# pre_amplify.net
KiCad netlist of a schematic drawn in Altium Designer
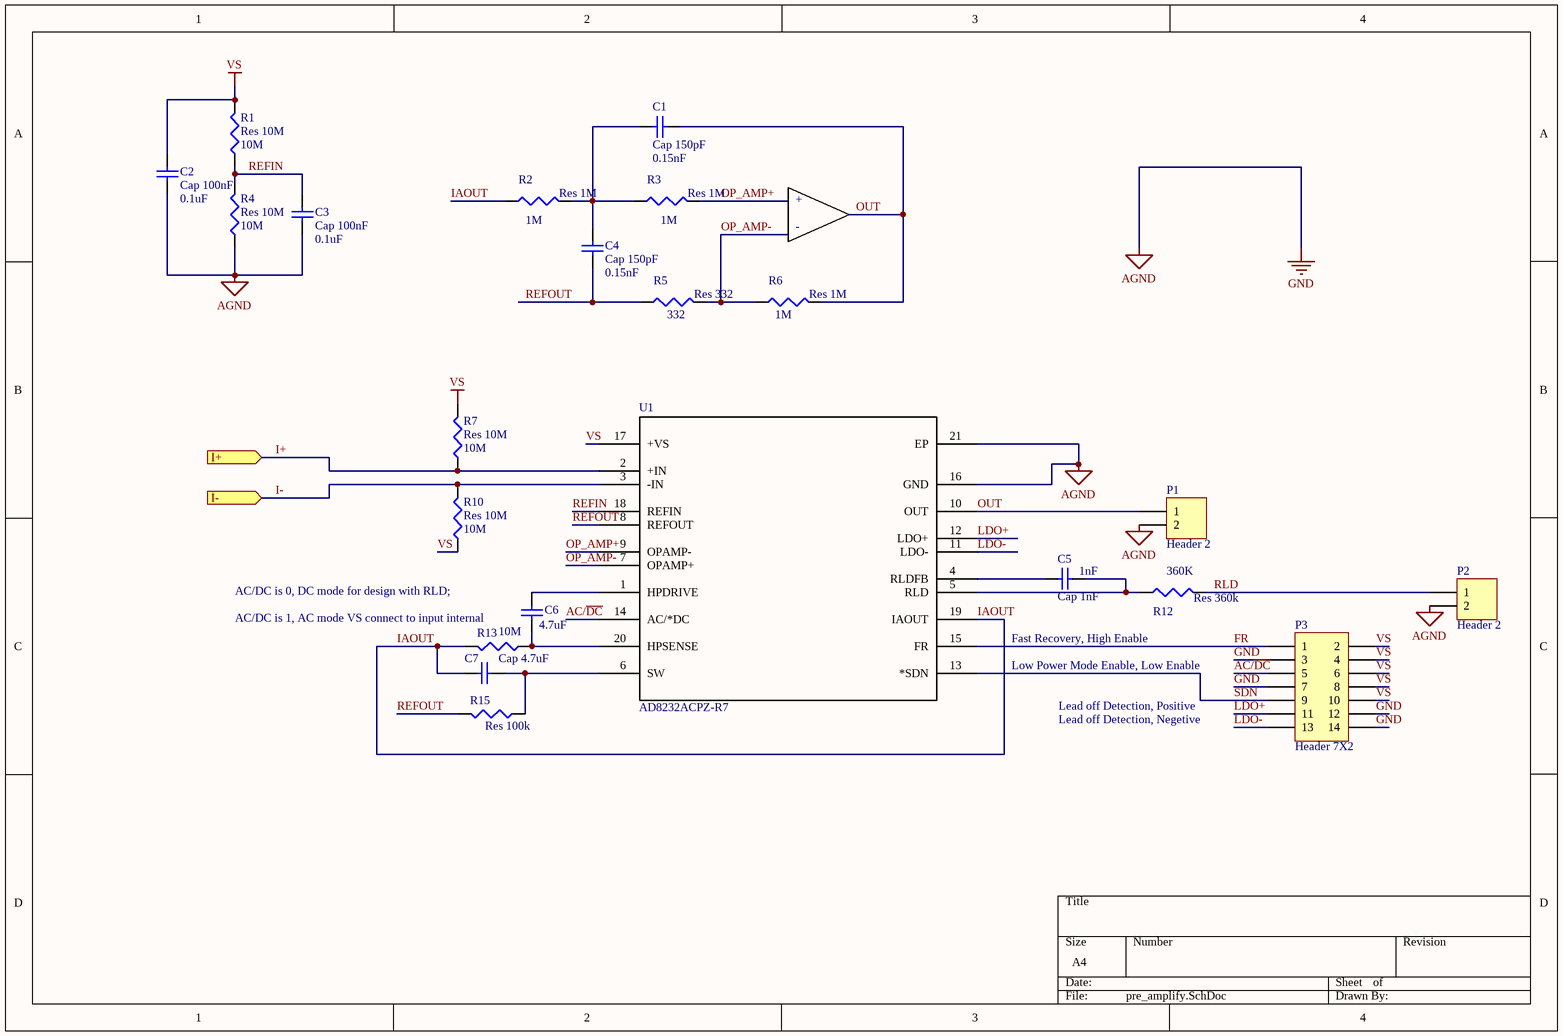
[diagram p0: pre_amplify.SchDoc]

(export (version "E")
  (design (tool "Eeschema 10.0.6"))
  (components
    (comp (ref "C1")
      (value "Cap 150pF")
      (footprint "0402")
      (description "Capacitor (Semiconductor SIM Model)")
      (fields (field (name "ALTIUM_VALUE") "0.15nF") (field (name "PUBLISHER") "Altium Limited"))
      (libsource (lib "Miscellaneous Devices") (part "Cap Semi"))
    )
    (comp (ref "C2")
      (value "Cap 100nF")
      (footprint "0402")
      (description "Capacitor (Semiconductor SIM Model)")
      (fields (field (name "ALTIUM_VALUE") "0.1uF") (field (name "PUBLISHER") "Altium Limited"))
      (libsource (lib "Miscellaneous Devices") (part "Cap Semi"))
    )
    (comp (ref "C3")
      (value "Cap 100nF")
      (footprint "0402")
      (description "Capacitor (Semiconductor SIM Model)")
      (fields (field (name "ALTIUM_VALUE") "0.1uF") (field (name "PUBLISHER") "Altium Limited"))
      (libsource (lib "Miscellaneous Devices") (part "Cap Semi"))
    )
    (comp (ref "C4")
      (value "Cap 150pF")
      (footprint "0402")
      (description "Capacitor (Semiconductor SIM Model)")
      (fields (field (name "ALTIUM_VALUE") "0.15nF") (field (name "PUBLISHER") "Altium Limited"))
      (libsource (lib "Miscellaneous Devices") (part "Cap Semi"))
    )
    (comp (ref "C5")
      (value "Cap 1nF")
      (footprint "0402")
      (description "Capacitor (Semiconductor SIM Model)")
      (fields (field (name "ALTIUM_VALUE") "1nF") (field (name "PUBLISHER") "Altium Limited"))
      (libsource (lib "Miscellaneous Devices") (part "Cap Semi"))
    )
    (comp (ref "C6")
      (value "4.7uF")
      (footprint "0402")
      (description "Capacitor (Semiconductor SIM Model)")
      (fields (field (name "Comment") "Cap 4.7uF") (field (name "PUBLISHER") "Altium Limited"))
      (libsource (lib "Miscellaneous Devices") (part "Cap Semi"))
    )
    (comp (ref "C7")
      (value "Cap 4.7uF")
      (footprint "0402")
      (description "Capacitor (Semiconductor SIM Model)")
      (fields (field (name "PUBLISHER") "Altium Limited"))
      (libsource (lib "Miscellaneous Devices") (part "Cap Semi"))
    )
    (comp (ref "P1")
      (value "Header 2")
      (footprint "HDR1X2")
      (description "Header, 2-Pin")
      (fields (field (name "PUBLISHER") "Altium Limited"))
      (libsource (lib "Miscellaneous Connectors") (part "Header 2"))
    )
    (comp (ref "P2")
      (value "Header 2")
      (footprint "HDR1X2")
      (description "Header, 2-Pin")
      (fields (field (name "PUBLISHER") "Altium Limited"))
      (libsource (lib "Miscellaneous Connectors") (part "Header 2"))
    )
    (comp (ref "P3")
      (value "Header 7X2")
      (footprint "HDR2X7")
      (description "Power, Control and Info Connection")
      (fields (field (name "PUBLISHER") "Altium Limited"))
      (libsource (lib "Miscellaneous Connectors") (part "Header 7X2"))
    )
    (comp (ref "R1")
      (value "Res 10M")
      (footprint "0402")
      (description "Resistor")
      (fields (field (name "ALTIUM_VALUE") "10M") (field (name "PUBLISHER") "Altium Limited"))
      (libsource (lib "Miscellaneous Devices") (part "Res3"))
    )
    (comp (ref "R2")
      (value "Res 1M")
      (footprint "0402")
      (description "Resistor")
      (fields (field (name "ALTIUM_VALUE") "1M") (field (name "PUBLISHER") "Altium Limited"))
      (libsource (lib "Miscellaneous Devices") (part "Res3"))
    )
    (comp (ref "R3")
      (value "Res 1M")
      (footprint "0402")
      (description "Resistor")
      (fields (field (name "ALTIUM_VALUE") "1M") (field (name "PUBLISHER") "Altium Limited"))
      (libsource (lib "Miscellaneous Devices") (part "Res3"))
    )
    (comp (ref "R4")
      (value "Res 10M")
      (footprint "0402")
      (description "Resistor")
      (fields (field (name "ALTIUM_VALUE") "10M") (field (name "PUBLISHER") "Altium Limited"))
      (libsource (lib "Miscellaneous Devices") (part "Res3"))
    )
    (comp (ref "R5")
      (value "Res 332")
      (footprint "0402")
      (description "Resistor")
      (fields (field (name "ALTIUM_VALUE") "332") (field (name "PUBLISHER") "Altium Limited"))
      (libsource (lib "Miscellaneous Devices") (part "Res3"))
    )
    (comp (ref "R6")
      (value "Res 1M")
      (footprint "0402")
      (description "Resistor")
      (fields (field (name "ALTIUM_VALUE") "1M") (field (name "PUBLISHER") "Altium Limited"))
      (libsource (lib "Miscellaneous Devices") (part "Res3"))
    )
    (comp (ref "R7")
      (value "Res 10M")
      (footprint "0402")
      (description "Resistor")
      (fields (field (name "ALTIUM_VALUE") "10M") (field (name "PUBLISHER") "Altium Limited"))
      (libsource (lib "Miscellaneous Devices") (part "Res3"))
    )
    (comp (ref "R10")
      (value "Res 10M")
      (footprint "0402")
      (description "Resistor")
      (fields (field (name "ALTIUM_VALUE") "10M") (field (name "PUBLISHER") "Altium Limited"))
      (libsource (lib "Miscellaneous Devices") (part "Res3"))
    )
    (comp (ref "R12")
      (value "Res 360k")
      (footprint "0402")
      (description "Resistor")
      (fields (field (name "ALTIUM_VALUE") "360K") (field (name "PUBLISHER") "Altium Limited"))
      (libsource (lib "Miscellaneous Devices") (part "Res3"))
    )
    (comp (ref "R13")
      (value "10M")
      (footprint "0402")
      (description "Resistor")
      (fields (field (name "Comment") "Res 10M") (field (name "PUBLISHER") "Altium Limited"))
      (libsource (lib "Miscellaneous Devices") (part "Res3"))
    )
    (comp (ref "R15")
      (value "Res 100k")
      (footprint "0402")
      (description "Resistor")
      (fields (field (name "PUBLISHER") "Altium Limited"))
      (libsource (lib "Miscellaneous Devices") (part "Res3"))
    )
    (comp (ref "U1")
      (value "AD8232ACPZ-R7")
      (footprint "CP_20_10")
      (description "Imported")
      (libsource (lib "2013-05-16_14-35-13") (part "AD8232ACPZ-R7"))
    )
  )
  (nets
    (net (code "1") (name "/AC{slash}~{DC}") (class "Default")
      (node (ref "P3") (pin "5") (pinfunction "5_5") (pintype "passive"))
      (node (ref "U1") (pin "14") (pinfunction "AC/*DC_14") (pintype "passive"))
    )
    (net (code "2") (name "/FR") (class "Default")
      (node (ref "P3") (pin "1") (pinfunction "1_1") (pintype "passive"))
      (node (ref "U1") (pin "15") (pinfunction "FR_15") (pintype "passive"))
    )
    (net (code "3") (name "/I+") (class "Default")
      (node (ref "R7") (pin "1") (pinfunction "1_1") (pintype "passive"))
      (node (ref "U1") (pin "2") (pinfunction "+IN_2") (pintype "passive"))
    )
    (net (code "4") (name "/I-") (class "Default")
      (node (ref "R10") (pin "2") (pinfunction "2_2") (pintype "passive"))
      (node (ref "U1") (pin "3") (pinfunction "-IN_3") (pintype "passive"))
    )
    (net (code "5") (name "/IAOUT") (class "Default")
      (node (ref "C7") (pin "2") (pinfunction "2_2") (pintype "passive"))
      (node (ref "R13") (pin "2") (pinfunction "2_2") (pintype "passive"))
      (node (ref "R2") (pin "1") (pinfunction "1_1") (pintype "passive"))
      (node (ref "U1") (pin "19") (pinfunction "IAOUT_19") (pintype "passive"))
    )
    (net (code "6") (name "/LDO+") (class "Default")
      (node (ref "P3") (pin "11") (pinfunction "11_11") (pintype "passive"))
      (node (ref "U1") (pin "12") (pinfunction "LDO+_12") (pintype "passive"))
    )
    (net (code "7") (name "/LDO-") (class "Default")
      (node (ref "P3") (pin "13") (pinfunction "13_13") (pintype "passive"))
      (node (ref "U1") (pin "11") (pinfunction "LDO-_11") (pintype "passive"))
    )
    (net (code "8") (name "/OP_AMP+") (class "Default")
      (node (ref "R3") (pin "2") (pinfunction "2_2") (pintype "passive"))
      (node (ref "U1") (pin "9") (pinfunction "OPAMP-_9") (pintype "passive"))
    )
    (net (code "9") (name "/OP_AMP-") (class "Default")
      (node (ref "R5") (pin "2") (pinfunction "2_2") (pintype "passive"))
      (node (ref "R6") (pin "1") (pinfunction "1_1") (pintype "passive"))
      (node (ref "U1") (pin "7") (pinfunction "OPAMP+_7") (pintype "passive"))
    )
    (net (code "10") (name "/OUT") (class "Default")
      (node (ref "C1") (pin "1") (pinfunction "1_1") (pintype "passive"))
      (node (ref "P1") (pin "1") (pinfunction "1_1") (pintype "passive"))
      (node (ref "R6") (pin "2") (pinfunction "2_2") (pintype "passive"))
      (node (ref "U1") (pin "10") (pinfunction "OUT_10") (pintype "passive"))
    )
    (net (code "11") (name "/REFIN") (class "Default")
      (node (ref "C3") (pin "2") (pinfunction "2_2") (pintype "passive"))
      (node (ref "R1") (pin "1") (pinfunction "1_1") (pintype "passive"))
      (node (ref "R4") (pin "2") (pinfunction "2_2") (pintype "passive"))
      (node (ref "U1") (pin "18") (pinfunction "REFIN_18") (pintype "passive"))
    )
    (net (code "12") (name "/REFOUT") (class "Default")
      (node (ref "C4") (pin "2") (pinfunction "2_2") (pintype "passive"))
      (node (ref "R15") (pin "2") (pinfunction "2_2") (pintype "passive"))
      (node (ref "R5") (pin "1") (pinfunction "1_1") (pintype "passive"))
      (node (ref "U1") (pin "8") (pinfunction "REFOUT_8") (pintype "passive"))
    )
    (net (code "13") (name "/RLD") (class "Default")
      (node (ref "P2") (pin "1") (pinfunction "1_1") (pintype "passive"))
      (node (ref "R12") (pin "2") (pinfunction "2_2") (pintype "passive"))
    )
    (net (code "14") (name "/SDN") (class "Default")
      (node (ref "P3") (pin "9") (pinfunction "9_9") (pintype "passive"))
      (node (ref "U1") (pin "13") (pinfunction "*SDN_13") (pintype "passive"))
    )
    (net (code "15") (name "AGND") (class "Default")
      (node (ref "C2") (pin "1") (pinfunction "1_1") (pintype "passive"))
      (node (ref "C3") (pin "1") (pinfunction "1_1") (pintype "passive"))
      (node (ref "P1") (pin "2") (pinfunction "2_2") (pintype "passive"))
      (node (ref "P2") (pin "2") (pinfunction "2_2") (pintype "passive"))
      (node (ref "P3") (pin "12") (pinfunction "12_12") (pintype "passive"))
      (node (ref "P3") (pin "14") (pinfunction "14_14") (pintype "passive"))
      (node (ref "P3") (pin "3") (pinfunction "3_3") (pintype "passive"))
      (node (ref "P3") (pin "7") (pinfunction "7_7") (pintype "passive"))
      (node (ref "R4") (pin "1") (pinfunction "1_1") (pintype "passive"))
      (node (ref "U1") (pin "16") (pinfunction "GND_16") (pintype "passive"))
      (node (ref "U1") (pin "21") (pinfunction "EP_21") (pintype "passive"))
    )
    (net (code "16") (name "Net-(C1-Pad2)") (class "Default")
      (node (ref "C1") (pin "2") (pinfunction "2_2") (pintype "passive"))
      (node (ref "C4") (pin "1") (pinfunction "1_1") (pintype "passive"))
      (node (ref "R2") (pin "2") (pinfunction "2_2") (pintype "passive"))
      (node (ref "R3") (pin "1") (pinfunction "1_1") (pintype "passive"))
    )
    (net (code "17") (name "Net-(U1-HPDRIVE)") (class "Default")
      (node (ref "C6") (pin "2") (pinfunction "2_2") (pintype "passive"))
      (node (ref "U1") (pin "1") (pinfunction "HPDRIVE_1") (pintype "passive"))
    )
    (net (code "18") (name "Net-(U1-HPSENSE)") (class "Default")
      (node (ref "C6") (pin "1") (pinfunction "1_1") (pintype "passive"))
      (node (ref "R13") (pin "1") (pinfunction "1_1") (pintype "passive"))
      (node (ref "U1") (pin "20") (pinfunction "HPSENSE_20") (pintype "passive"))
    )
    (net (code "19") (name "Net-(U1-RLD)") (class "Default")
      (node (ref "C5") (pin "1") (pinfunction "1_1") (pintype "passive"))
      (node (ref "R12") (pin "1") (pinfunction "1_1") (pintype "passive"))
      (node (ref "U1") (pin "5") (pinfunction "RLD_5") (pintype "passive"))
    )
    (net (code "20") (name "Net-(U1-RLDFB)") (class "Default")
      (node (ref "C5") (pin "2") (pinfunction "2_2") (pintype "passive"))
      (node (ref "U1") (pin "4") (pinfunction "RLDFB_4") (pintype "passive"))
    )
    (net (code "21") (name "Net-(U1-SW)") (class "Default")
      (node (ref "C7") (pin "1") (pinfunction "1_1") (pintype "passive"))
      (node (ref "R15") (pin "1") (pinfunction "1_1") (pintype "passive"))
      (node (ref "U1") (pin "6") (pinfunction "SW_6") (pintype "passive"))
    )
    (net (code "22") (name "VS") (class "Default")
      (node (ref "C2") (pin "2") (pinfunction "2_2") (pintype "passive"))
      (node (ref "P3") (pin "10") (pinfunction "10_10") (pintype "passive"))
      (node (ref "P3") (pin "2") (pinfunction "2_2") (pintype "passive"))
      (node (ref "P3") (pin "4") (pinfunction "4_4") (pintype "passive"))
      (node (ref "P3") (pin "6") (pinfunction "6_6") (pintype "passive"))
      (node (ref "P3") (pin "8") (pinfunction "8_8") (pintype "passive"))
      (node (ref "R1") (pin "2") (pinfunction "2_2") (pintype "passive"))
      (node (ref "R10") (pin "1") (pinfunction "1_1") (pintype "passive"))
      (node (ref "R7") (pin "2") (pinfunction "2_2") (pintype "passive"))
      (node (ref "U1") (pin "17") (pinfunction "+VS_17") (pintype "passive"))
    )
  )
)
